# OctoSlime_Splitter.net
KiCad netlist of a schematic drawn in EasyEDA Pro
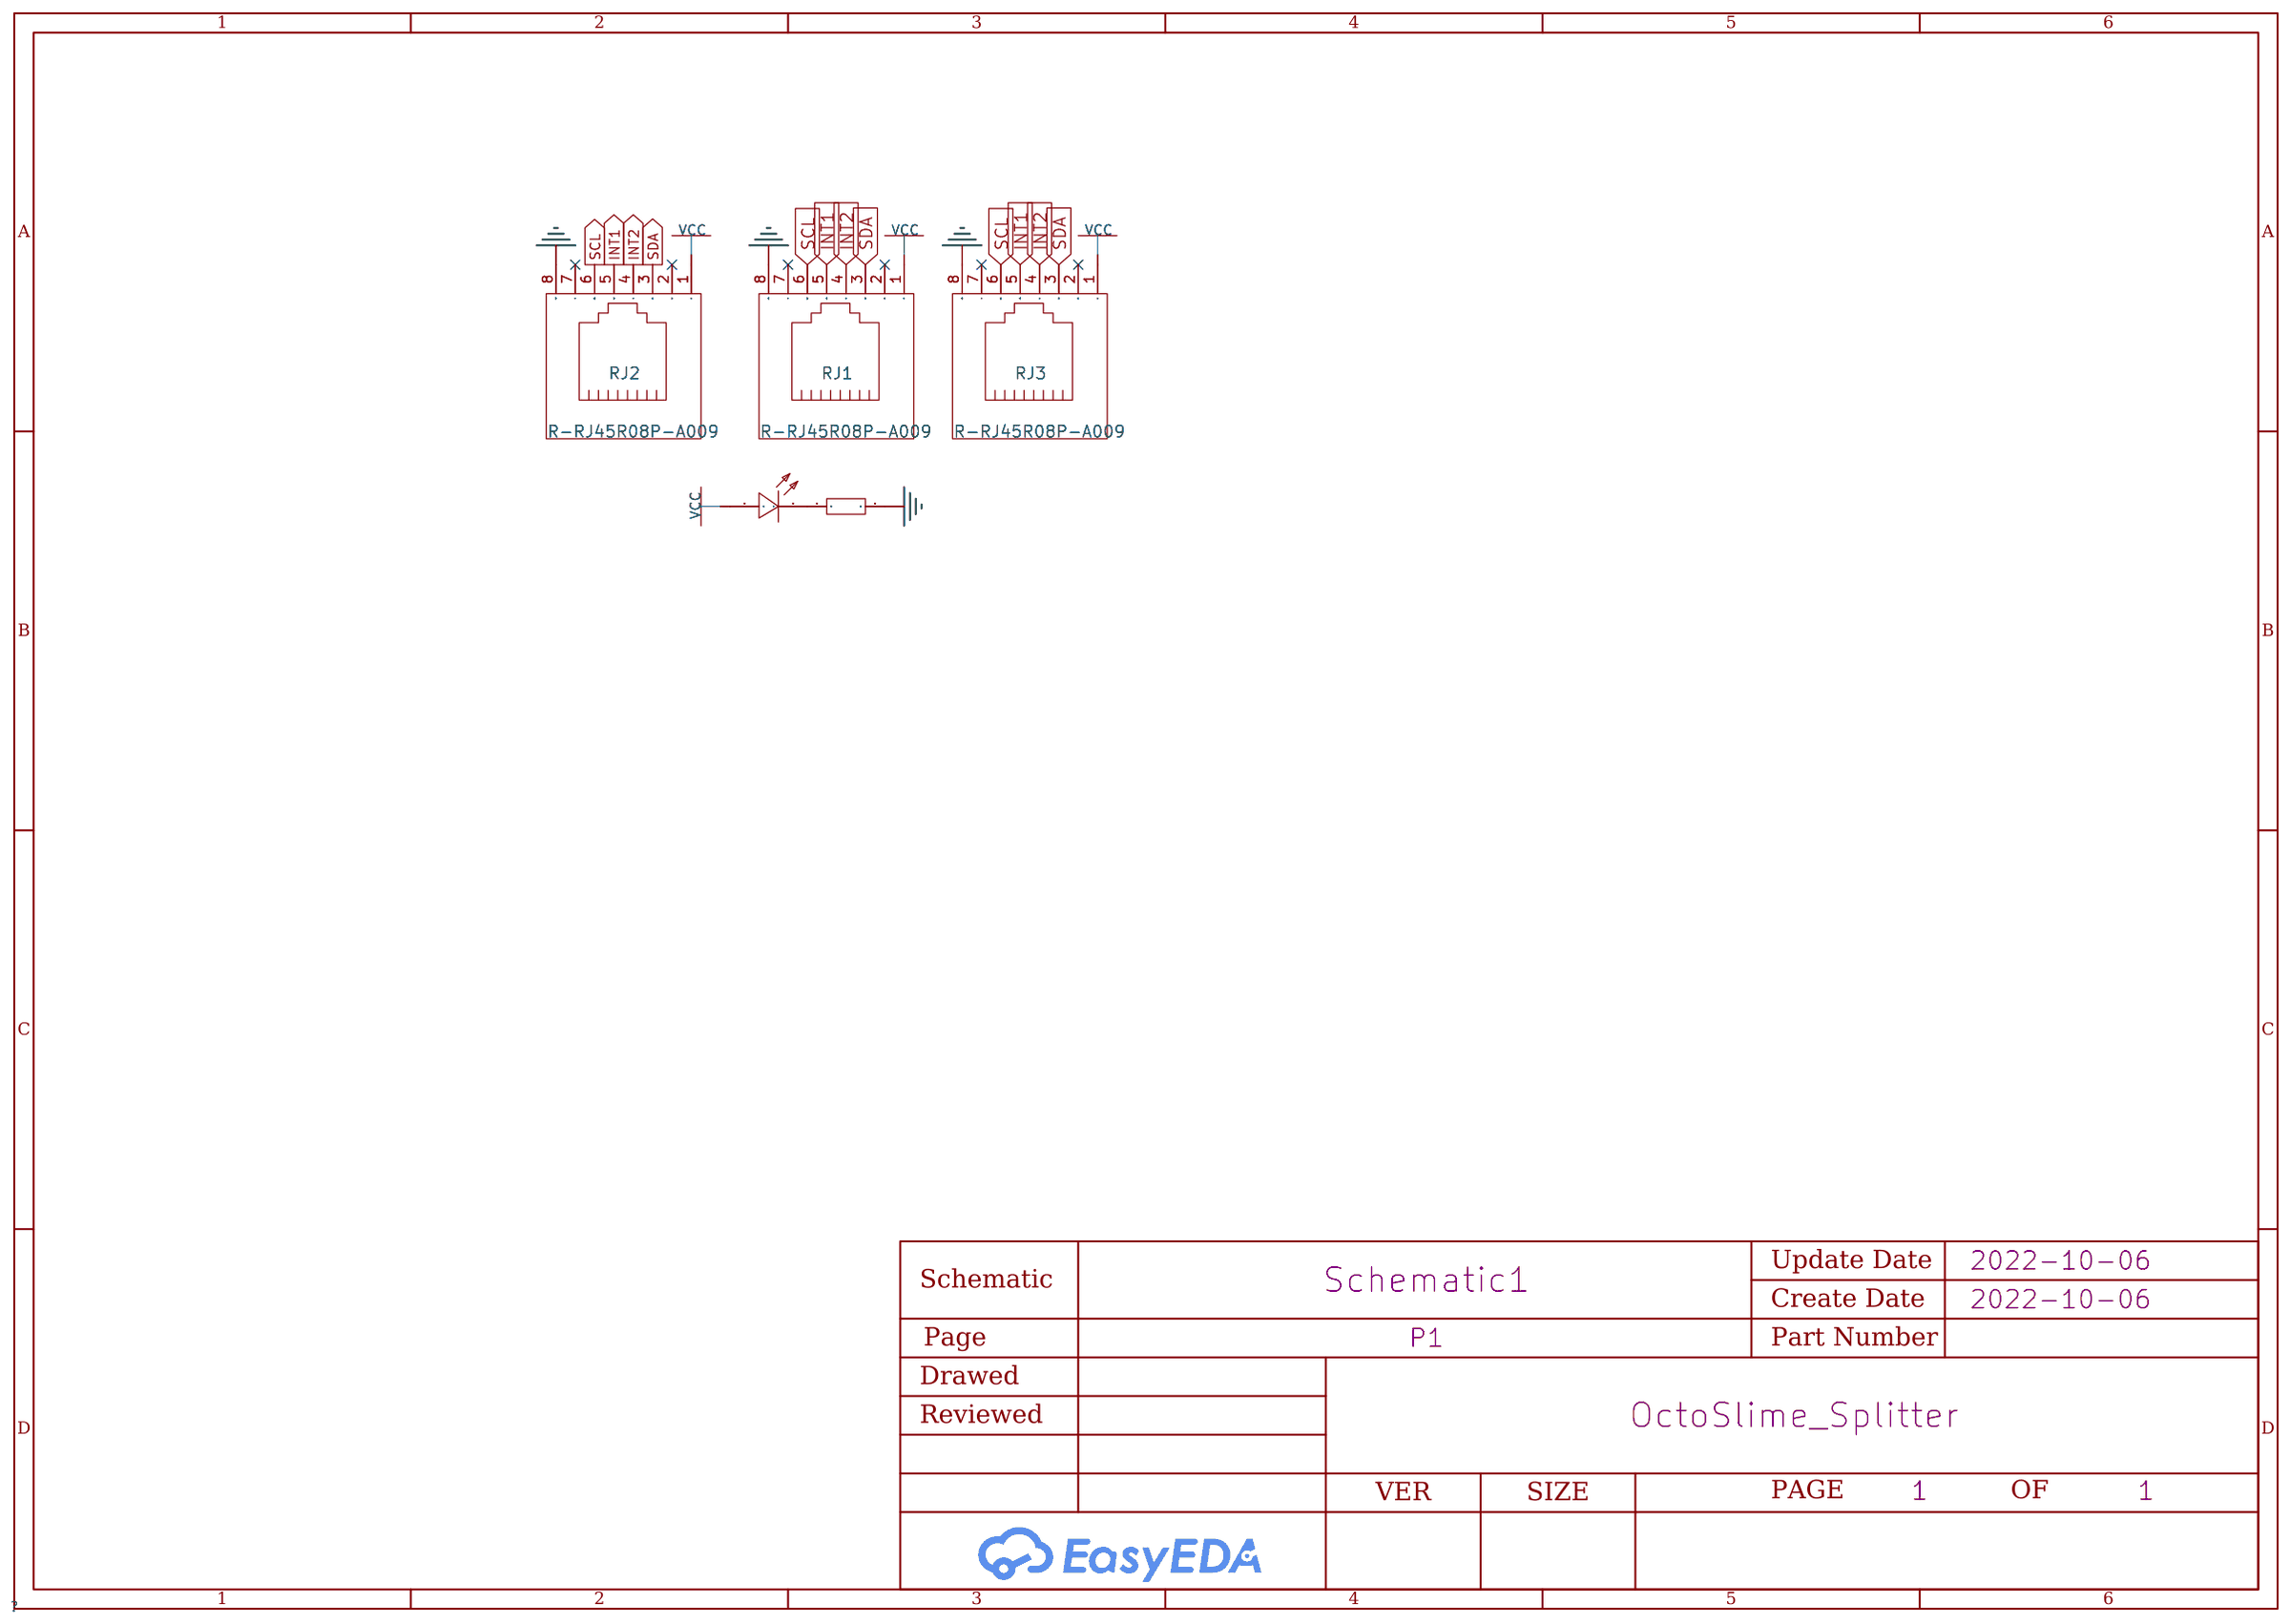
[diagram p0: schematic sheet]

(export (version "E")
  (design (tool "Eeschema 10.0.6"))
  (components
    (comp (ref "LED1")
      (value "~")
      (footprint "easyedapro:LED0603-R-RD")
      (fields (field (name "Manufacturer Part") "KT-0603R") (field (name "Manufacturer") "KENTO"))
      (libsource (lib "easyedapro") (part "KT-0603R"))
    )
    (comp (ref "R3")
      (value "330Ω")
      (footprint "easyedapro:R0603")
      (description "电阻类型:厚膜电阻;阻值:330Ω;精度:±1%;功率:1/10W;温度系数:±100ppm/;最大工作电压:75V;工作温度范围:-55~+155;")
      (fields
        (field (name "Manufacturer Part") "0603WAF3300T5E")
        (field (name "Manufacturer") "UNI-ROYAL(厚声)")
      )
      (libsource (lib "easyedapro") (part "0603WAF3300T5E"))
    )
    (comp (ref "RJ1")
      (value "R-RJ45R08P-A009")
      (footprint "easyedapro:RJ45-TH_R-RJ45R08P-A009")
      (fields (field (name "Manufacturer") "Ckmtw(灿科盟)"))
      (libsource (lib "easyedapro") (part "R-RJ45R08P-A009"))
    )
    (comp (ref "RJ2")
      (value "R-RJ45R08P-A009")
      (footprint "easyedapro:RJ45-TH_R-RJ45R08P-A009")
      (fields (field (name "Manufacturer") "Ckmtw(灿科盟)"))
      (libsource (lib "easyedapro") (part "R-RJ45R08P-A009"))
    )
    (comp (ref "RJ3")
      (value "R-RJ45R08P-A009")
      (footprint "easyedapro:RJ45-TH_R-RJ45R08P-A009")
      (fields (field (name "Manufacturer") "Ckmtw(灿科盟)"))
      (libsource (lib "easyedapro") (part "R-RJ45R08P-A009"))
    )
  )
  (nets
    (net (code "1") (name "GND") (class "Default")
      (node (ref "R3") (pin "2") (pinfunction "2_2") (pintype "input"))
      (node (ref "RJ1") (pin "8") (pinfunction "8_8") (pintype "input"))
      (node (ref "RJ2") (pin "8") (pinfunction "8_8") (pintype "input"))
      (node (ref "RJ3") (pin "8") (pinfunction "8_8") (pintype "input"))
    )
    (net (code "2") (name "INT1") (class "Default")
      (node (ref "RJ1") (pin "5") (pinfunction "5_5") (pintype "input"))
      (node (ref "RJ2") (pin "5") (pinfunction "5_5") (pintype "input"))
      (node (ref "RJ3") (pin "5") (pinfunction "5_5") (pintype "input"))
    )
    (net (code "3") (name "INT2") (class "Default")
      (node (ref "RJ1") (pin "4") (pinfunction "4_4") (pintype "input"))
      (node (ref "RJ2") (pin "4") (pinfunction "4_4") (pintype "input"))
      (node (ref "RJ3") (pin "4") (pinfunction "4_4") (pintype "input"))
    )
    (net (code "4") (name "Net-(LED1-K)") (class "Default")
      (node (ref "LED1") (pin "2") (pinfunction "K_2") (pintype "input"))
      (node (ref "R3") (pin "1") (pinfunction "1_1") (pintype "input"))
    )
    (net (code "5") (name "SCL") (class "Default")
      (node (ref "RJ1") (pin "6") (pinfunction "6_6") (pintype "input"))
      (node (ref "RJ2") (pin "6") (pinfunction "6_6") (pintype "input"))
      (node (ref "RJ3") (pin "6") (pinfunction "6_6") (pintype "input"))
    )
    (net (code "6") (name "SDA") (class "Default")
      (node (ref "RJ1") (pin "3") (pinfunction "3_3") (pintype "input"))
      (node (ref "RJ2") (pin "3") (pinfunction "3_3") (pintype "input"))
      (node (ref "RJ3") (pin "3") (pinfunction "3_3") (pintype "input"))
    )
    (net (code "7") (name "VCC") (class "Default")
      (node (ref "LED1") (pin "1") (pinfunction "A_1") (pintype "input"))
      (node (ref "RJ1") (pin "1") (pinfunction "1_1") (pintype "input"))
      (node (ref "RJ2") (pin "1") (pinfunction "1_1") (pintype "input"))
      (node (ref "RJ3") (pin "1") (pinfunction "1_1") (pintype "input"))
    )
    (net (code "8") (name "unconnected-(RJ1-Pad2)") (class "Default")
      (node (ref "RJ1") (pin "2") (pinfunction "2_2") (pintype "input+no_connect"))
    )
    (net (code "9") (name "unconnected-(RJ1-Pad7)") (class "Default")
      (node (ref "RJ1") (pin "7") (pinfunction "7_7") (pintype "input+no_connect"))
    )
    (net (code "10") (name "unconnected-(RJ2-Pad2)") (class "Default")
      (node (ref "RJ2") (pin "2") (pinfunction "2_2") (pintype "input+no_connect"))
    )
    (net (code "11") (name "unconnected-(RJ2-Pad7)") (class "Default")
      (node (ref "RJ2") (pin "7") (pinfunction "7_7") (pintype "input+no_connect"))
    )
    (net (code "12") (name "unconnected-(RJ3-Pad2)") (class "Default")
      (node (ref "RJ3") (pin "2") (pinfunction "2_2") (pintype "input+no_connect"))
    )
    (net (code "13") (name "unconnected-(RJ3-Pad7)") (class "Default")
      (node (ref "RJ3") (pin "7") (pinfunction "7_7") (pintype "input+no_connect"))
    )
  )
)
